# USB.net
KiCad netlist of a schematic drawn in Altium Designer
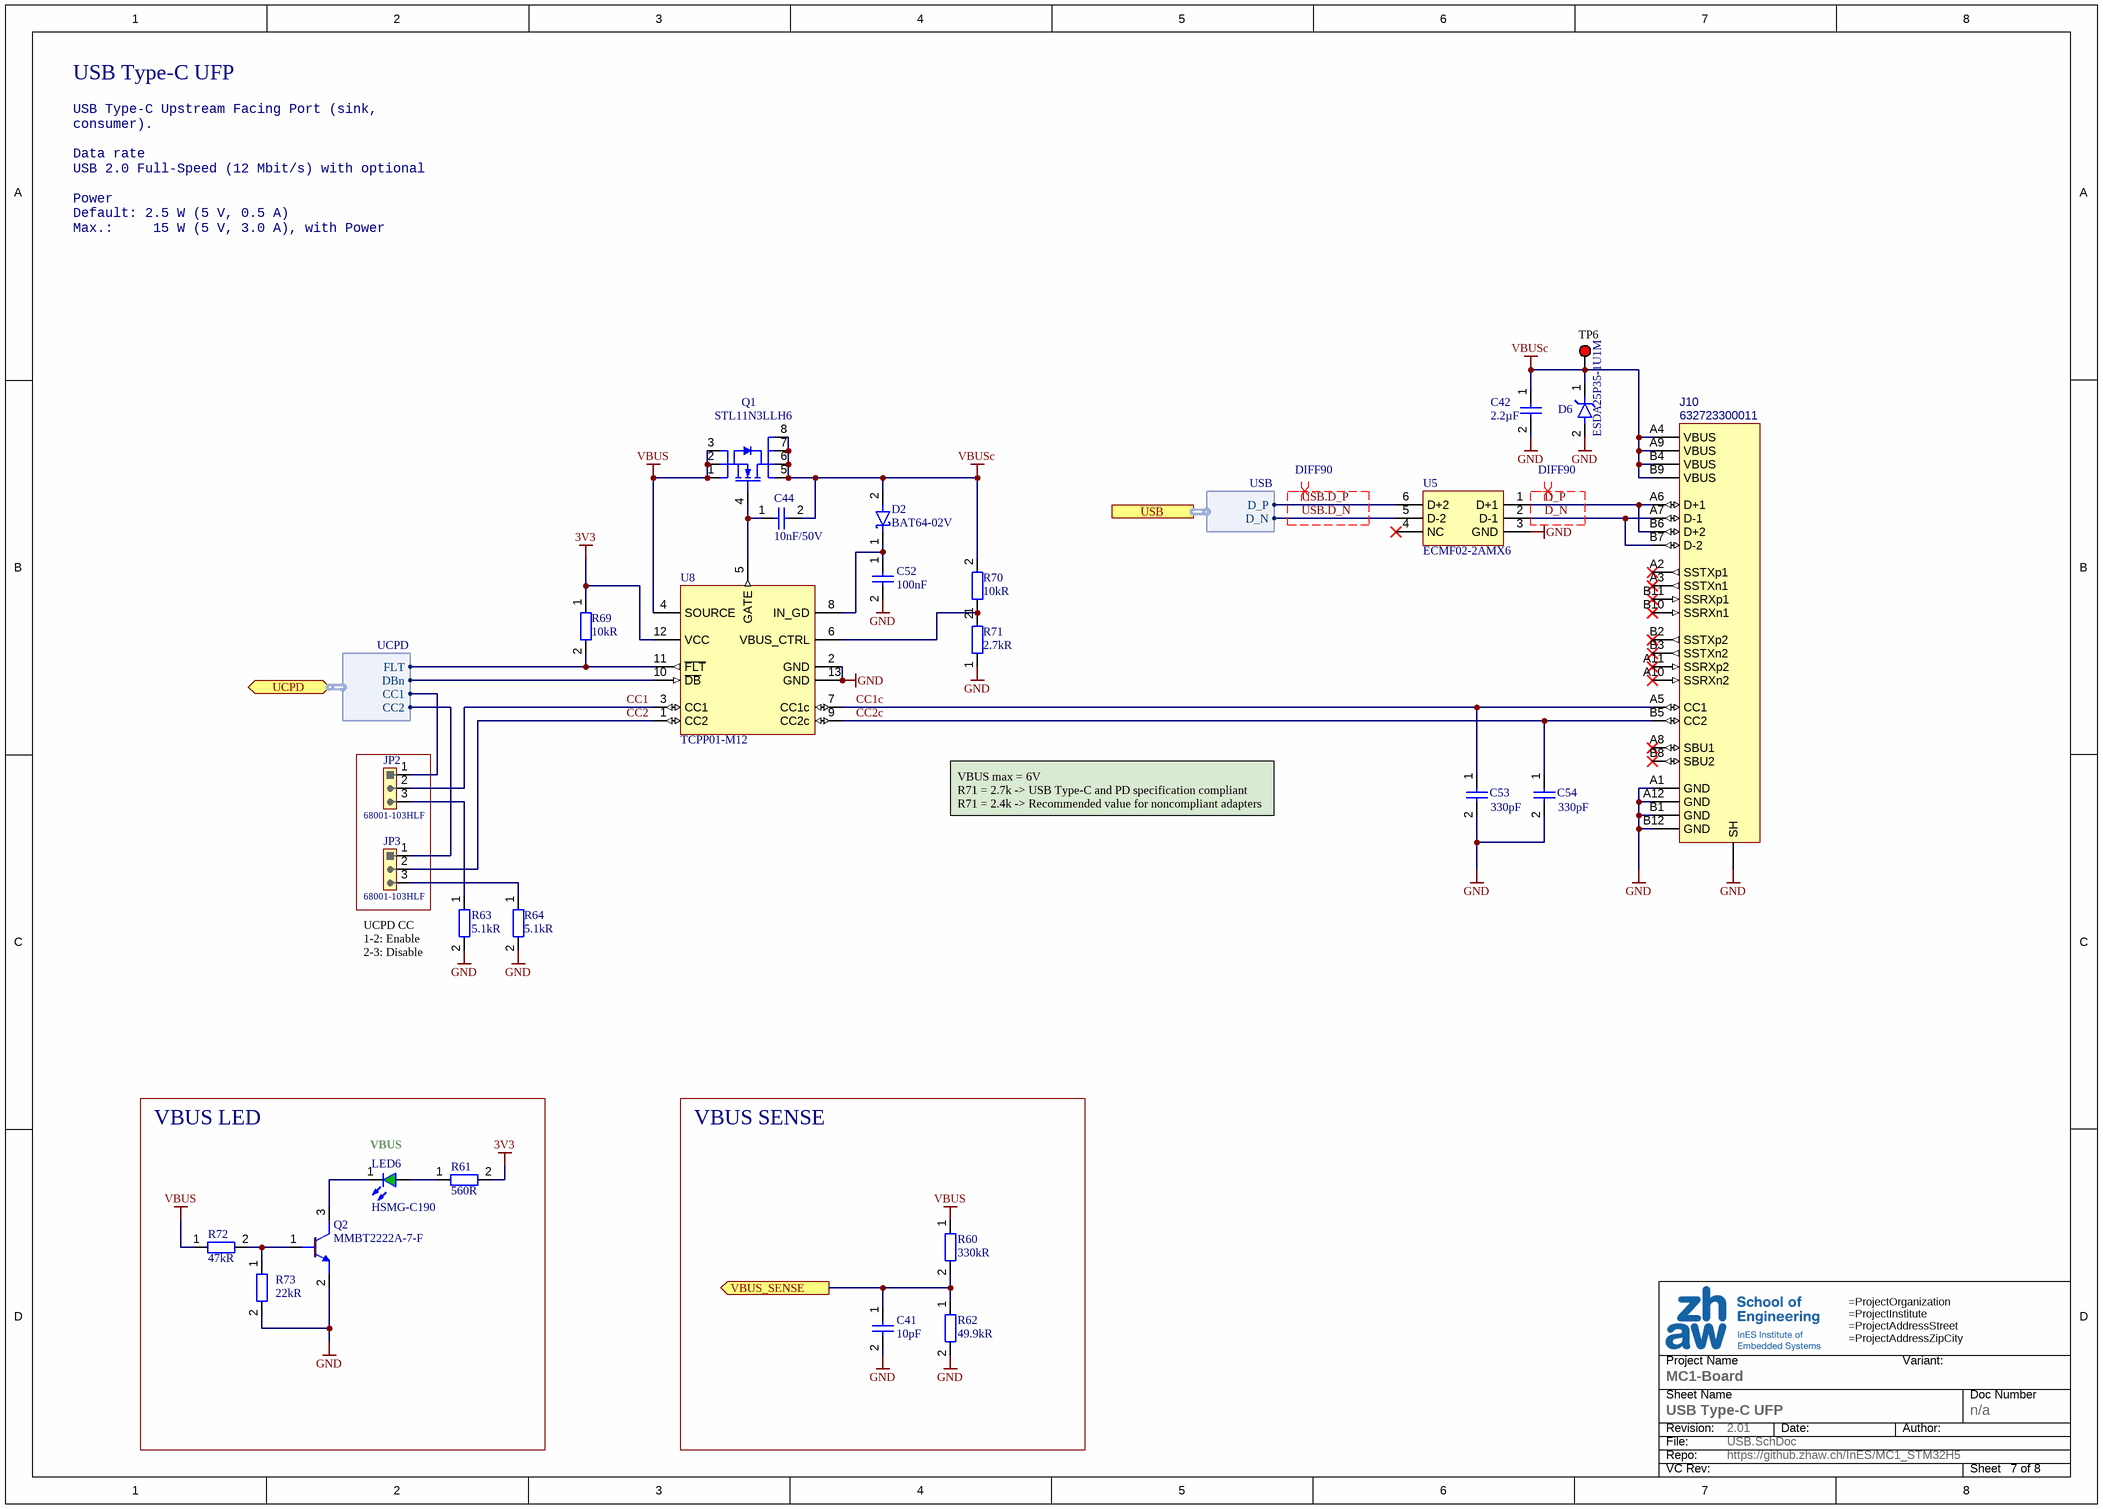
[diagram p0: USB.SchDoc]

(export (version "E")
  (design (tool "Eeschema 10.0.6"))
  (components
    (comp (ref "C41")
      (value "10pF")
      (footprint "CAPC1608X80N")
      (description "Cap MLCC, 10pF, 50V, C0G, 5%, 0603")
      (fields (field (name "TOLERANCE") "5%") (field (name "Comment") "10pF/50V"))
      (libsource (lib "ZHAW on Altium 365") (part "CAP-NP-2"))
    )
    (comp (ref "C42")
      (value "2.2µF")
      (footprint "CAPC1608X80N")
      (description "Cap MLCC, 2.2uF, 10V, X7R, 10%, 0603")
      (fields (field (name "TOLERANCE") "10%") (field (name "Comment") "2.2uF/10V"))
      (libsource (lib "ZHAW on Altium 365") (part "CAP-NP-2"))
    )
    (comp (ref "C44")
      (value "10nF/50V")
      (footprint "CAPC1005X50N")
      (description "Cap MLCC, 10nF, 50V, X7R, 10%, 0402")
      (fields (field (name "TOLERANCE") "10%"))
      (libsource (lib "ZHAW on Altium 365") (part "CAP-NP-2"))
    )
    (comp (ref "C52")
      (value "100nF")
      (footprint "CAPC1608X80N")
      (description "Cap MLCC, 100nF, 50V, X7R, 10%, 0603")
      (fields (field (name "TOLERANCE") "10%") (field (name "Comment") "100nF/50V"))
      (libsource (lib "ZHAW on Altium 365") (part "CAP-NP-2"))
    )
    (comp (ref "C53")
      (value "330pF")
      (footprint "CAPC1005X50N")
      (description "Cap MLCC, 330pF, 50V, C0G, 5%, 0402")
      (fields (field (name "TOLERANCE") "5%") (field (name "Comment") "330pF/50V"))
      (libsource (lib "ZHAW on Altium 365") (part "CAP-NP-2"))
    )
    (comp (ref "C54")
      (value "330pF")
      (footprint "CAPC1005X50N")
      (description "Cap MLCC, 330pF, 50V, C0G, 5%, 0402")
      (fields (field (name "TOLERANCE") "5%") (field (name "Comment") "330pF/50V"))
      (libsource (lib "ZHAW on Altium 365") (part "CAP-NP-2"))
    )
    (comp (ref "D2")
      (value "BAT64-02V")
      (footprint "SODFL160X65-2N")
      (description "Schottky Diode, 40V, 250mA, SOD-523FL-2")
      (fields (field (name "VOLTAGE") "40V"))
      (libsource (lib "ZHAW on Altium 365") (part "D-SKY-KA-2"))
    )
    (comp (ref "D6")
      (value "ESDA25P35-1U1M")
      (footprint "DFN110P160X60-2L")
      (description "TVS Diode, unidirectional, 22V, 35A, 1400W, 1610 (0603)")
      (libsource (lib "ZHAW on Altium 365") (part "D-TVS-KA-2"))
    )
    (comp (ref "J10")
      (value "632723300011")
      (footprint "WE_632723300011")
      (description "USB-C, 24 Pin, Pitch 500um, 20V, Horizontal, SMD/THT, L11.2B8.74H2.96")
      (fields (field (name "MANUFACTURER") "Wurth Elektronik"))
      (libsource (lib "ZHAW on Altium 365") (part "CN-USB-C-24"))
    )
    (comp (ref "JP2")
      (value "68001-103HLF")
      (footprint "HD254_1x3_MV")
      (description "Header, 1x3 Pin, Pitch 2.54mm, Male, Vertical, THT")
      (fields (field (name "MANUFACTURER") "FCI"))
      (libsource (lib "ZHAW on Altium 365") (part "HDR-1x03-M-3"))
    )
    (comp (ref "JP3")
      (value "68001-103HLF")
      (footprint "HD254_1x3_MV")
      (description "Header, 1x3 Pin, Pitch 2.54mm, Male, Vertical, THT")
      (fields (field (name "MANUFACTURER") "FCI"))
      (libsource (lib "ZHAW on Altium 365") (part "HDR-1x03-M-3"))
    )
    (comp (ref "LED6")
      (value "HSMG-C190")
      (footprint "LEDSC160X80X80-2Lgn")
      (description "LED, Green, 20mA, 2.2V, 0603")
      (libsource (lib "ZHAW on Altium 365") (part "LED-GN-KA-2"))
    )
    (comp (ref "Q1")
      (value "STL11N3LLH6")
      (footprint "PowerFLAT65P300X315X80-8+1")
      (description "MOSFET N-enh, 30V, 11A, 44Ap, 6mR, 50W, PowerFLAT 3.3 x 3.3")
      (fields (field (name "POWER") "50W") (field (name "VOLTAGE") "30V"))
      (libsource (lib "ZHAW on Altium 365") (part "NEMOS-SSSGDDDD-8"))
    )
    (comp (ref "Q2")
      (value "MMBT2222A-7-F")
      (footprint "SOT95P235X120-3N")
      (description "Transistor NPN, 40V, 600mA, 310mW, SOT-23-3")
      (fields (field (name "VOLTAGE") "40V") (field (name "POWER") "310mW"))
      (libsource (lib "ZHAW on Altium 365") (part "BJT-NPN-BEC-3"))
    )
    (comp (ref "R60")
      (value "330kR")
      (footprint "RESC1608X45N")
      (description "Res, 330kR, 1%, 0.1W, 0603")
      (fields (field (name "TOLERANCE") "1%") (field (name "POWER") "100mW"))
      (libsource (lib "") (part "RES-2_3"))
    )
    (comp (ref "R61")
      (value "560R")
      (footprint "RESC1608X45N")
      (description "Res, 560R, 1%, 100mW, 0603")
      (fields (field (name "TOLERANCE") "1%") (field (name "POWER") "100mW"))
      (libsource (lib "ZHAW on Altium 365") (part "RES-2"))
    )
    (comp (ref "R62")
      (value "49.9kR")
      (footprint "RESC1608X45N")
      (description "Res, 49.9kR, 1%, 100mW, 0603")
      (fields (field (name "POWER") "100mW") (field (name "TOLERANCE") "1%"))
      (libsource (lib "") (part "RES-2_3"))
    )
    (comp (ref "R63")
      (value "5.1kR")
      (footprint "RESC1005X35N")
      (description "Res, 5.1kR, 1%, 0.063W, 0402")
      (fields (field (name "TOLERANCE") "1%") (field (name "POWER") "63mW"))
      (libsource (lib "") (part "RES-2_1"))
    )
    (comp (ref "R64")
      (value "5.1kR")
      (footprint "RESC1005X35N")
      (description "Res, 5.1kR, 1%, 0.063W, 0402")
      (fields (field (name "TOLERANCE") "1%") (field (name "POWER") "63mW"))
      (libsource (lib "") (part "RES-2_1"))
    )
    (comp (ref "R69")
      (value "10kR")
      (footprint "RESC1005X35N")
      (description "Res, 10kR, 1%, 0.063W, 0402")
      (fields (field (name "TOLERANCE") "1%") (field (name "POWER") "63mW"))
      (libsource (lib "") (part "RES-2_1"))
    )
    (comp (ref "R70")
      (value "10kR")
      (footprint "RESC1005X35N")
      (description "Res, 10kR, 1%, 0.063W, 0402")
      (fields (field (name "TOLERANCE") "1%") (field (name "POWER") "63mW"))
      (libsource (lib "ZHAW on Altium 365") (part "RES-2"))
    )
    (comp (ref "R71")
      (value "2.7kR")
      (footprint "RESC1005X35N")
      (description "Res, 2.7kR, 1%, 0.063W, 0402")
      (fields (field (name "POWER") "63mW") (field (name "TOLERANCE") "1%"))
      (libsource (lib "") (part "RES-2_2"))
    )
    (comp (ref "R72")
      (value "47kR")
      (footprint "RESC1608X45N")
      (description "Res, 47kR, 1%, 0.1W, 0603")
      (fields (field (name "POWER") "100mW") (field (name "TOLERANCE") "1%"))
      (libsource (lib "ZHAW on Altium 365") (part "RES-2"))
    )
    (comp (ref "R73")
      (value "22kR")
      (footprint "RESC1608X45N")
      (description "Res, 22kR, 1%, 0.1W, 0603")
      (fields (field (name "TOLERANCE") "1%") (field (name "POWER") "100mW"))
      (libsource (lib "") (part "RES-2_3"))
    )
    (comp (ref "TP6")
      (value "5000")
      (footprint "KSTN-5000")
      (description "Test Point, Red, D2.5H4.6, THT, closed ring D1.25")
      (libsource (lib "ZHAW on Altium 365") (part "TP-RD"))
    )
    (comp (ref "U5")
      (value "ECMF02-2AMX6")
      (footprint "QFN50P150X170X50-6N")
      (libsource (lib "ZHAW on Altium 365") (part "EMCMISC-ECMF02-2-6"))
    )
    (comp (ref "U8")
      (value "TCPP01-M12")
      (footprint "QFN50P300X300X100-13T145X145N")
      (description "USB Type-C and Power Delivery Protection, 2.7...22V, QFN-12")
      (libsource (lib "ZHAW on Altium 365") (part "PWR-TCPP01-M12-13"))
    )
  )
  (nets
    (net (code "3") (name "/CC1") (class "Default")
      (node (ref "JP2") (pin "2") (pinfunction "2_2") (pintype "passive"))
      (node (ref "U8") (pin "3") (pinfunction "CC1_3") (pintype "bidirectional"))
    )
    (net (code "4") (name "/CC1c") (class "Default")
      (node (ref "C53") (pin "1") (pinfunction "1_1") (pintype "passive"))
      (node (ref "J10") (pin "A5") (pinfunction "CC1_A5") (pintype "bidirectional"))
      (node (ref "U8") (pin "7") (pinfunction "CC1c_7") (pintype "bidirectional"))
    )
    (net (code "5") (name "/CC2") (class "Default")
      (node (ref "JP3") (pin "2") (pinfunction "2_2") (pintype "passive"))
      (node (ref "U8") (pin "1") (pinfunction "CC2_1") (pintype "bidirectional"))
    )
    (net (code "6") (name "/CC2c") (class "Default")
      (node (ref "C54") (pin "1") (pinfunction "1_1") (pintype "passive"))
      (node (ref "J10") (pin "B5") (pinfunction "CC2_B5") (pintype "bidirectional"))
      (node (ref "U8") (pin "9") (pinfunction "CC2c_9") (pintype "bidirectional"))
    )
    (net (code "7") (name "/DBn") (class "Default")
      (node (ref "U8") (pin "10") (pinfunction "~{DB}_10") (pintype "input"))
    )
    (net (code "8") (name "/D_N") (class "Default")
      (node (ref "J10") (pin "A7") (pinfunction "D-1_A7") (pintype "bidirectional"))
      (node (ref "J10") (pin "B7") (pinfunction "D-2_B7") (pintype "bidirectional"))
      (node (ref "U5") (pin "2") (pinfunction "D-1_2") (pintype "passive"))
    )
    (net (code "9") (name "/D_P") (class "Default")
      (node (ref "J10") (pin "A6") (pinfunction "D+1_A6") (pintype "bidirectional"))
      (node (ref "J10") (pin "B6") (pinfunction "D+2_B6") (pintype "bidirectional"))
      (node (ref "U5") (pin "1") (pinfunction "D+1_1") (pintype "passive"))
    )
    (net (code "10") (name "/FLT") (class "Default")
      (node (ref "R69") (pin "2") (pinfunction "2_2") (pintype "passive"))
      (node (ref "U8") (pin "11") (pinfunction "~{FLT}_11") (pintype "output"))
    )
    (net (code "11") (name "/USB.D_N") (class "Default")
      (node (ref "U5") (pin "5") (pinfunction "D-2_5") (pintype "passive"))
    )
    (net (code "12") (name "/USB.D_P") (class "Default")
      (node (ref "U5") (pin "6") (pinfunction "D+2_6") (pintype "passive"))
    )
    (net (code "13") (name "/VBUS_SENSE") (class "Default")
      (node (ref "C41") (pin "1") (pinfunction "1_1") (pintype "passive"))
      (node (ref "R60") (pin "2") (pinfunction "2_2") (pintype "passive"))
      (node (ref "R62") (pin "1") (pinfunction "1_1") (pintype "passive"))
    )
    (net (code "16") (name "3V3") (class "Default")
      (node (ref "R61") (pin "2") (pinfunction "2_2") (pintype "passive"))
      (node (ref "R69") (pin "1") (pinfunction "1_1") (pintype "passive"))
      (node (ref "U8") (pin "12") (pinfunction "VCC_12") (pintype "power_in"))
    )
    (net (code "17") (name "GND") (class "Default")
      (node (ref "C41") (pin "2") (pinfunction "2_2") (pintype "passive"))
      (node (ref "C42") (pin "2") (pinfunction "2_2") (pintype "passive"))
      (node (ref "C52") (pin "2") (pinfunction "2_2") (pintype "passive"))
      (node (ref "C53") (pin "2") (pinfunction "2_2") (pintype "passive"))
      (node (ref "C54") (pin "2") (pinfunction "2_2") (pintype "passive"))
      (node (ref "D6") (pin "2") (pinfunction "A_2") (pintype "passive"))
      (node (ref "J10") (pin "A1") (pinfunction "GND_A1") (pintype "power_in"))
      (node (ref "J10") (pin "A12") (pinfunction "GND_A12") (pintype "power_in"))
      (node (ref "J10") (pin "B1") (pinfunction "GND_B1") (pintype "power_in"))
      (node (ref "J10") (pin "B12") (pinfunction "GND_B12") (pintype "power_in"))
      (node (ref "J10") (pin "SH") (pinfunction "SH_SH") (pintype "passive"))
      (node (ref "Q2") (pin "2") (pinfunction "E_2") (pintype "passive"))
      (node (ref "R62") (pin "2") (pinfunction "2_2") (pintype "passive"))
      (node (ref "R63") (pin "2") (pinfunction "2_2") (pintype "passive"))
      (node (ref "R64") (pin "2") (pinfunction "2_2") (pintype "passive"))
      (node (ref "R71") (pin "1") (pinfunction "1_1") (pintype "passive"))
      (node (ref "R73") (pin "2") (pinfunction "2_2") (pintype "passive"))
      (node (ref "U5") (pin "3") (pinfunction "GND_3") (pintype "power_in"))
      (node (ref "U8") (pin "13") (pinfunction "GND_13") (pintype "power_in"))
      (node (ref "U8") (pin "2") (pinfunction "GND_2") (pintype "power_in"))
    )
    (net (code "18") (name "Net-(D2-Cathode)") (class "Default")
      (node (ref "C52") (pin "1") (pinfunction "1_1") (pintype "passive"))
      (node (ref "D2") (pin "1") (pinfunction "Cathode_1") (pintype "passive"))
      (node (ref "U8") (pin "8") (pinfunction "IN_GD_8") (pintype "power_in"))
    )
    (net (code "19") (name "Net-(JP2-Pad3)") (class "Default")
      (node (ref "JP2") (pin "3") (pinfunction "3_3") (pintype "passive"))
      (node (ref "R63") (pin "1") (pinfunction "1_1") (pintype "passive"))
    )
    (net (code "20") (name "Net-(JP3-Pad3)") (class "Default")
      (node (ref "JP3") (pin "3") (pinfunction "3_3") (pintype "passive"))
      (node (ref "R64") (pin "1") (pinfunction "1_1") (pintype "passive"))
    )
    (net (code "21") (name "Net-(LED6-A)") (class "Default")
      (node (ref "LED6") (pin "2") (pinfunction "A_2") (pintype "passive"))
      (node (ref "R61") (pin "1") (pinfunction "1_1") (pintype "passive"))
    )
    (net (code "22") (name "Net-(LED6-K)") (class "Default")
      (node (ref "LED6") (pin "1") (pinfunction "K_1") (pintype "passive"))
      (node (ref "Q2") (pin "3") (pinfunction "C_3") (pintype "passive"))
    )
    (net (code "23") (name "Net-(Q1-G)") (class "Default")
      (node (ref "C44") (pin "1") (pinfunction "1_1") (pintype "passive"))
      (node (ref "Q1") (pin "4") (pinfunction "G_4") (pintype "passive"))
      (node (ref "U8") (pin "5") (pinfunction "GATE_5") (pintype "output"))
    )
    (net (code "24") (name "Net-(Q2-B)") (class "Default")
      (node (ref "Q2") (pin "1") (pinfunction "B_1") (pintype "passive"))
      (node (ref "R72") (pin "2") (pinfunction "2_2") (pintype "passive"))
      (node (ref "R73") (pin "1") (pinfunction "1_1") (pintype "passive"))
    )
    (net (code "25") (name "Net-(U8-VBUS_CTRL)") (class "Default")
      (node (ref "R70") (pin "1") (pinfunction "1_1") (pintype "passive"))
      (node (ref "R71") (pin "2") (pinfunction "2_2") (pintype "passive"))
      (node (ref "U8") (pin "6") (pinfunction "VBUS_CTRL_6") (pintype "passive"))
    )
    (net (code "26") (name "VBUS") (class "Default")
      (node (ref "Q1") (pin "1") (pinfunction "S_1") (pintype "passive"))
      (node (ref "Q1") (pin "2") (pinfunction "S_2") (pintype "passive"))
      (node (ref "Q1") (pin "3") (pinfunction "S_3") (pintype "passive"))
      (node (ref "R60") (pin "1") (pinfunction "1_1") (pintype "passive"))
      (node (ref "R72") (pin "1") (pinfunction "1_1") (pintype "passive"))
      (node (ref "U8") (pin "4") (pinfunction "SOURCE_4") (pintype "power_in"))
    )
    (net (code "27") (name "VBUSc") (class "Default")
      (node (ref "C42") (pin "1") (pinfunction "1_1") (pintype "passive"))
      (node (ref "C44") (pin "2") (pinfunction "2_2") (pintype "passive"))
      (node (ref "D2") (pin "2") (pinfunction "Anode_2") (pintype "passive"))
      (node (ref "D6") (pin "1") (pinfunction "A_1") (pintype "passive"))
      (node (ref "J10") (pin "A4") (pinfunction "VBUS_A4") (pintype "power_in"))
      (node (ref "J10") (pin "A9") (pinfunction "VBUS_A9") (pintype "power_in"))
      (node (ref "J10") (pin "B4") (pinfunction "VBUS_B4") (pintype "power_in"))
      (node (ref "J10") (pin "B9") (pinfunction "VBUS_B9") (pintype "power_in"))
      (node (ref "Q1") (pin "5") (pinfunction "D_5") (pintype "passive"))
      (node (ref "Q1") (pin "6") (pinfunction "D_6") (pintype "passive"))
      (node (ref "Q1") (pin "7") (pinfunction "D_7") (pintype "passive"))
      (node (ref "Q1") (pin "8") (pinfunction "D_8") (pintype "passive"))
      (node (ref "R70") (pin "2") (pinfunction "2_2") (pintype "passive"))
      (node (ref "TP6") (pin "1") (pinfunction "1_1") (pintype "passive"))
    )
    (net (code "28") (name "unconnected-(J10-SBU1-PadA8)") (class "Default")
      (node (ref "J10") (pin "A8") (pinfunction "SBU1_A8") (pintype "bidirectional+no_connect"))
    )
    (net (code "29") (name "unconnected-(J10-SBU2-PadB8)") (class "Default")
      (node (ref "J10") (pin "B8") (pinfunction "SBU2_B8") (pintype "bidirectional+no_connect"))
    )
    (net (code "30") (name "unconnected-(J10-SSRXn1-PadB10)") (class "Default")
      (node (ref "J10") (pin "B10") (pinfunction "SSRXn1_B10") (pintype "input+no_connect"))
    )
    (net (code "31") (name "unconnected-(J10-SSRXn2-PadA10)") (class "Default")
      (node (ref "J10") (pin "A10") (pinfunction "SSRXn2_A10") (pintype "input+no_connect"))
    )
    (net (code "32") (name "unconnected-(J10-SSRXp1-PadB11)") (class "Default")
      (node (ref "J10") (pin "B11") (pinfunction "SSRXp1_B11") (pintype "input+no_connect"))
    )
    (net (code "33") (name "unconnected-(J10-SSRXp2-PadA11)") (class "Default")
      (node (ref "J10") (pin "A11") (pinfunction "SSRXp2_A11") (pintype "input+no_connect"))
    )
    (net (code "34") (name "unconnected-(J10-SSTXn1-PadA3)") (class "Default")
      (node (ref "J10") (pin "A3") (pinfunction "SSTXn1_A3") (pintype "output+no_connect"))
    )
    (net (code "35") (name "unconnected-(J10-SSTXn2-PadB3)") (class "Default")
      (node (ref "J10") (pin "B3") (pinfunction "SSTXn2_B3") (pintype "output+no_connect"))
    )
    (net (code "36") (name "unconnected-(J10-SSTXp1-PadA2)") (class "Default")
      (node (ref "J10") (pin "A2") (pinfunction "SSTXp1_A2") (pintype "output+no_connect"))
    )
    (net (code "37") (name "unconnected-(J10-SSTXp2-PadB2)") (class "Default")
      (node (ref "J10") (pin "B2") (pinfunction "SSTXp2_B2") (pintype "output+no_connect"))
    )
    (net (code "38") (name "unconnected-(JP2-Pad1)") (class "Default")
      (node (ref "JP2") (pin "1") (pinfunction "1_1") (pintype "passive"))
    )
    (net (code "39") (name "unconnected-(JP3-Pad1)") (class "Default")
      (node (ref "JP3") (pin "1") (pinfunction "1_1") (pintype "passive"))
    )
    (net (code "40") (name "unconnected-(U5-NC-Pad4)") (class "Default")
      (node (ref "U5") (pin "4") (pinfunction "NC_4") (pintype "passive+no_connect"))
    )
  )
)
